# AUDIO_CODEC.net
KiCad netlist of a schematic drawn in Altium Designer
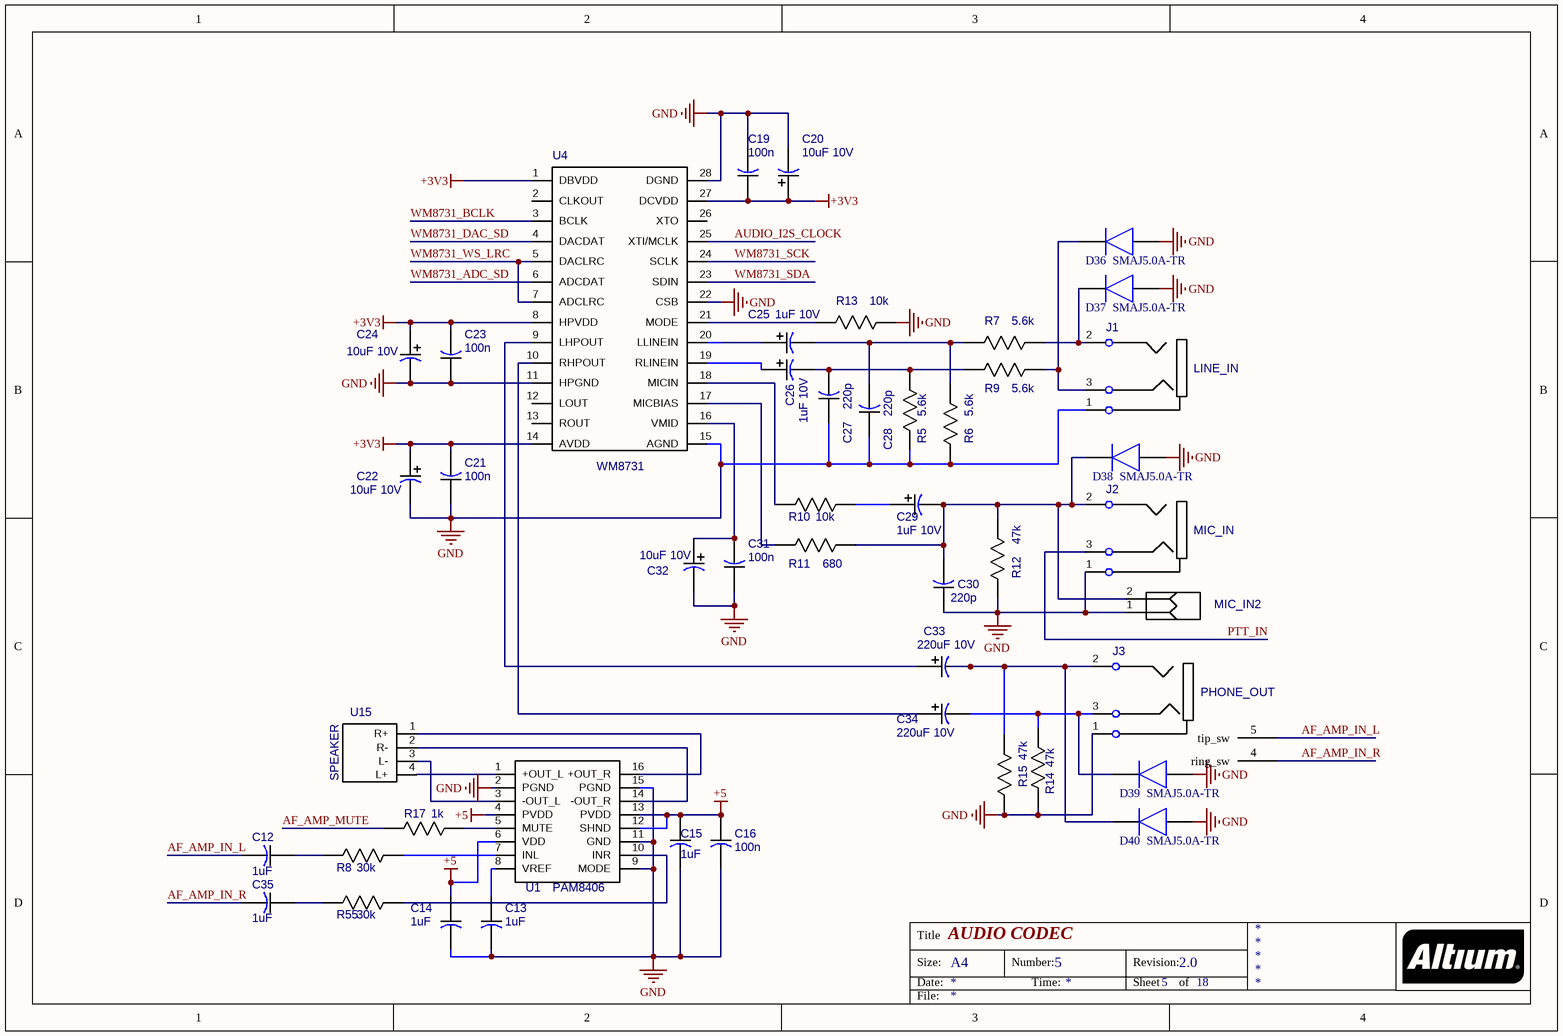
[diagram p0: AUDIO CODEC.SchDoc]

(export (version "E")
  (design (tool "Eeschema 10.0.6"))
  (components
    (comp (ref "C12")
      (value "1uF")
      (footprint "CAP_0805")
      (description "CAP_0805")
      (libsource (lib "*") (part "CAP_0805"))
    )
    (comp (ref "C13")
      (value "1uF")
      (footprint "CAP_0805")
      (description "CAP_0805")
      (libsource (lib "*") (part "CAP_0805"))
    )
    (comp (ref "C14")
      (value "1uF")
      (footprint "CAP_0805")
      (description "CAP_0805")
      (libsource (lib "*") (part "CAP_0805"))
    )
    (comp (ref "C15")
      (value "1uF")
      (footprint "CAP_0805")
      (description "CAP_0805")
      (libsource (lib "*") (part "CAP_0805"))
    )
    (comp (ref "C16")
      (value "100n")
      (footprint "CAP_0805")
      (description "CAP_0805")
      (libsource (lib "*") (part "CAP_0805"))
    )
    (comp (ref "C19")
      (value "100n")
      (footprint "CAP_0805")
      (description "CAP_0805")
      (libsource (lib "*") (part "CAP_0805"))
    )
    (comp (ref "C20")
      (value "10uF 10V")
      (footprint "CAPAE_4.3x4.3h5.4")
      (description "CAPAE_4.3x4.3h5.4")
      (libsource (lib "*") (part "CAPAE_4.3x4.3h5.4"))
    )
    (comp (ref "C21")
      (value "100n")
      (footprint "CAP_0805")
      (description "CAP_0805")
      (libsource (lib "*") (part "CAP_0805"))
    )
    (comp (ref "C22")
      (value "10uF 10V")
      (footprint "CAPAE_4.3x4.3h5.4")
      (description "CAPAE_4.3x4.3h5.4")
      (libsource (lib "*") (part "CAPAE_4.3x4.3h5.4"))
    )
    (comp (ref "C23")
      (value "100n")
      (footprint "CAP_0805")
      (description "CAP_0805")
      (libsource (lib "*") (part "CAP_0805"))
    )
    (comp (ref "C24")
      (value "10uF 10V")
      (footprint "CAPAE_4.3x4.3h5.4")
      (description "CAPAE_4.3x4.3h5.4")
      (libsource (lib "*") (part "CAPAE_4.3x4.3h5.4"))
    )
    (comp (ref "C25")
      (value "1uF 10V")
      (footprint "CAPAE_4.3x4.3h5.4")
      (description "CAPAE_4.3x4.3h5.4")
      (libsource (lib "*") (part "CAPAE_4.3x4.3h5.4"))
    )
    (comp (ref "C26")
      (value "1uF 10V")
      (footprint "CAPAE_4.3x4.3h5.4")
      (description "CAPAE_4.3x4.3h5.4")
      (libsource (lib "*") (part "CAPAE_4.3x4.3h5.4"))
    )
    (comp (ref "C27")
      (value "220p")
      (footprint "CAP_0805")
      (description "CAP_0805")
      (libsource (lib "*") (part "CAP_0805"))
    )
    (comp (ref "C28")
      (value "220p")
      (footprint "CAP_0805")
      (description "CAP_0805")
      (libsource (lib "*") (part "CAP_0805"))
    )
    (comp (ref "C29")
      (value "1uF 10V")
      (footprint "CAPAE_4.3x4.3h5.4")
      (description "CAPAE_4.3x4.3h5.4")
      (libsource (lib "*") (part "CAPAE_4.3x4.3h5.4"))
    )
    (comp (ref "C30")
      (value "220p")
      (footprint "CAP_0805")
      (description "CAP_0805")
      (libsource (lib "*") (part "CAP_0805"))
    )
    (comp (ref "C31")
      (value "100n")
      (footprint "CAP_0805")
      (description "CAP_0805")
      (libsource (lib "*") (part "CAP_0805"))
    )
    (comp (ref "C32")
      (value "10uF 10V")
      (footprint "CAPAE_4.3x4.3h5.4")
      (description "CAPAE_4.3x4.3h5.4")
      (libsource (lib "*") (part "CAPAE_4.3x4.3h5.4"))
    )
    (comp (ref "C33")
      (value "220uF 10V")
      (footprint "EEEFC_sizeС")
      (description "CAPAE_4.3x4.3h5.4")
      (libsource (lib "*") (part "CAPAE_4.3x4.3h5.4"))
    )
    (comp (ref "C34")
      (value "220uF 10V")
      (footprint "EEEFC_sizeС")
      (description "CAPAE_4.3x4.3h5.4")
      (libsource (lib "*") (part "CAPAE_4.3x4.3h5.4"))
    )
    (comp (ref "C35")
      (value "1uF")
      (footprint "CAP_0805")
      (description "CAP_0805")
      (libsource (lib "*") (part "CAP_0805"))
    )
    (comp (ref "D36")
      (value "SMAJ5.0A-TR")
      (footprint "SamacSys:SMBJ36CATR")
      (description "Diode")
      (fields
        (field (name "MANUFACTURER_PART_NUMBER") "SMLVT3V3")
        (field (name "MOUSER PART NUMBER") "511-SMLVT3V3")
      )
      (libsource (lib "*") (part "SMLVT3V3"))
    )
    (comp (ref "D37")
      (value "SMAJ5.0A-TR")
      (footprint "SamacSys:SMBJ36CATR")
      (description "Diode")
      (fields
        (field (name "MANUFACTURER_PART_NUMBER") "SMLVT3V3")
        (field (name "MOUSER PART NUMBER") "511-SMLVT3V3")
      )
      (libsource (lib "*") (part "SMLVT3V3"))
    )
    (comp (ref "D38")
      (value "SMAJ5.0A-TR")
      (footprint "SamacSys:SMBJ36CATR")
      (description "Diode")
      (fields
        (field (name "MANUFACTURER_PART_NUMBER") "SMLVT3V3")
        (field (name "MOUSER PART NUMBER") "511-SMLVT3V3")
      )
      (libsource (lib "*") (part "SMLVT3V3"))
    )
    (comp (ref "D39")
      (value "SMAJ5.0A-TR")
      (footprint "SamacSys:SMBJ36CATR")
      (description "Diode")
      (fields
        (field (name "MANUFACTURER_PART_NUMBER") "SMLVT3V3")
        (field (name "MOUSER PART NUMBER") "511-SMLVT3V3")
      )
      (libsource (lib "*") (part "SMLVT3V3"))
    )
    (comp (ref "D40")
      (value "SMAJ5.0A-TR")
      (footprint "SamacSys:SMBJ36CATR")
      (description "Diode")
      (fields
        (field (name "MANUFACTURER_PART_NUMBER") "SMLVT3V3")
        (field (name "MOUSER PART NUMBER") "511-SMLVT3V3")
      )
      (libsource (lib "*") (part "SMLVT3V3"))
    )
    (comp (ref "J1")
      (value "LINE_IN")
      (footprint "SJ1-3525NG")
      (description "SJ1-3525NG")
      (libsource (lib "*") (part "SJ1-3523N"))
    )
    (comp (ref "J2")
      (value "MIC_IN")
      (footprint "SJ1-3525NG")
      (description "SJ1-3525NG")
      (libsource (lib "*") (part "SJ1-3523N"))
    )
    (comp (ref "J3")
      (value "PHONE_OUT")
      (footprint "SJ1-3525NG")
      (description "SJ1-3525NG")
      (libsource (lib "") (part "SJ1-3523N_1"))
    )
    (comp (ref "MIС_IN2")
      (value "MIС_IN2")
      (footprint "51022-0200")
      (description "2 Pin")
      (libsource (lib "*") (part "51022-0200"))
    )
    (comp (ref "R5")
      (value "5.6k")
      (footprint "RES_0805")
      (description "RES_0805")
      (libsource (lib "*") (part "RES_0805"))
    )
    (comp (ref "R6")
      (value "5.6k")
      (footprint "RES_0805")
      (description "RES_0805")
      (libsource (lib "*") (part "RES_0805"))
    )
    (comp (ref "R7")
      (value "5.6k")
      (footprint "RES_0805")
      (description "RES_0805")
      (libsource (lib "*") (part "RES_0805"))
    )
    (comp (ref "R8")
      (value "30k")
      (footprint "RES_0805")
      (description "RES_0805")
      (libsource (lib "*") (part "RES_0805"))
    )
    (comp (ref "R9")
      (value "5.6k")
      (footprint "RES_0805")
      (description "RES_0805")
      (libsource (lib "*") (part "RES_0805"))
    )
    (comp (ref "R10")
      (value "10k")
      (footprint "RES_0805")
      (description "RES_0805")
      (libsource (lib "*") (part "RES_0805"))
    )
    (comp (ref "R11")
      (value "680")
      (footprint "RES_0805")
      (description "RES_0805")
      (libsource (lib "*") (part "RES_0805"))
    )
    (comp (ref "R12")
      (value "47k")
      (footprint "RES_0805")
      (description "RES_0805")
      (libsource (lib "*") (part "RES_0805"))
    )
    (comp (ref "R13")
      (value "10k")
      (footprint "RES_0805")
      (description "RES_0805")
      (libsource (lib "*") (part "RES_0805"))
    )
    (comp (ref "R14")
      (value "47k")
      (footprint "RES_0805")
      (description "RES_0805")
      (libsource (lib "*") (part "RES_0805"))
    )
    (comp (ref "R15")
      (value "47k")
      (footprint "RES_0805")
      (description "RES_0805")
      (libsource (lib "*") (part "RES_0805"))
    )
    (comp (ref "R17")
      (value "1k")
      (footprint "RES_0805")
      (description "RES_0805")
      (libsource (lib "*") (part "RES_0805"))
    )
    (comp (ref "R55")
      (value "30k")
      (footprint "RES_0805")
      (description "RES_0805")
      (libsource (lib "*") (part "RES_0805"))
    )
    (comp (ref "U1") (value "PAM8406") (footprint "PAM8403") (libsource (lib "MOTHERBOARD") (part "PAM8406")))
    (comp (ref "U4") (value "WM8731") (footprint "WM8731") (libsource (lib "*") (part "WM8731")))
    (comp (ref "U15")
      (value "SPEAKER")
      (footprint "speaker conn")
      (description "4 pins conn")
      (libsource (lib "MOTHERBOARD") (part "speaker conn"))
    )
  )
  (nets
    (net (code "1") (name "+3V3") (class "Default")
      (node (ref "C19") (pin "1") (pinfunction "1_1") (pintype "passive"))
      (node (ref "C20") (pin "1") (pinfunction "PLUS_1") (pintype "passive"))
      (node (ref "C21") (pin "2") (pinfunction "2_2") (pintype "passive"))
      (node (ref "C22") (pin "1") (pinfunction "PLUS_1") (pintype "passive"))
      (node (ref "C23") (pin "2") (pinfunction "2_2") (pintype "passive"))
      (node (ref "C24") (pin "1") (pinfunction "PLUS_1") (pintype "passive"))
      (node (ref "U4") (pin "1") (pinfunction "DBVDD_1") (pintype "passive"))
      (node (ref "U4") (pin "14") (pinfunction "AVDD_14") (pintype "passive"))
      (node (ref "U4") (pin "27") (pinfunction "DCVDD_27") (pintype "passive"))
      (node (ref "U4") (pin "8") (pinfunction "HPVDD_8") (pintype "passive"))
    )
    (net (code "2") (name "+5") (class "Default")
      (node (ref "C14") (pin "1") (pinfunction "1_1") (pintype "passive"))
      (node (ref "C15") (pin "1") (pinfunction "1_1") (pintype "passive"))
      (node (ref "C16") (pin "1") (pinfunction "1_1") (pintype "passive"))
      (node (ref "U1") (pin "12") (pinfunction "SHND_12") (pintype "passive"))
      (node (ref "U1") (pin "13") (pinfunction "PVDD_13") (pintype "passive"))
      (node (ref "U1") (pin "4") (pinfunction "PVDD_4") (pintype "passive"))
      (node (ref "U1") (pin "6") (pinfunction "VDD_6") (pintype "passive"))
    )
    (net (code "3") (name "/AF_AMP_IN_L") (class "Default")
      (node (ref "C12") (pin "2") (pinfunction "2_2") (pintype "passive"))
      (node (ref "J3") (pin "5") (pinfunction "tip_sw_5") (pintype "passive"))
    )
    (net (code "4") (name "/AF_AMP_IN_R") (class "Default")
      (node (ref "C35") (pin "2") (pinfunction "2_2") (pintype "passive"))
      (node (ref "J3") (pin "4") (pinfunction "ring_sw_4") (pintype "passive"))
    )
    (net (code "5") (name "/AF_AMP_MUTE") (class "Default")
      (node (ref "R17") (pin "2") (pinfunction "2_2") (pintype "passive"))
    )
    (net (code "6") (name "/AUDIO_I2S_CLOCK") (class "Default")
      (node (ref "U4") (pin "25") (pinfunction "XTI/MCLK_25") (pintype "passive"))
    )
    (net (code "7") (name "/PTT_IN") (class "Default")
      (node (ref "J2") (pin "3") (pinfunction "ring_3") (pintype "passive"))
    )
    (net (code "8") (name "/WM8731_ADC_SD") (class "Default")
      (node (ref "U4") (pin "6") (pinfunction "ADCDAT_6") (pintype "passive"))
    )
    (net (code "9") (name "/WM8731_BCLK") (class "Default")
      (node (ref "U4") (pin "3") (pinfunction "BCLK_3") (pintype "passive"))
    )
    (net (code "10") (name "/WM8731_DAC_SD") (class "Default")
      (node (ref "U4") (pin "4") (pinfunction "DACDAT_4") (pintype "passive"))
    )
    (net (code "11") (name "/WM8731_SCK") (class "Default")
      (node (ref "U4") (pin "24") (pinfunction "SCLK_24") (pintype "passive"))
    )
    (net (code "12") (name "/WM8731_SDA") (class "Default")
      (node (ref "U4") (pin "23") (pinfunction "SDIN_23") (pintype "passive"))
    )
    (net (code "13") (name "/WM8731_WS_LRC") (class "Default")
      (node (ref "U4") (pin "5") (pinfunction "DACLRC_5") (pintype "passive"))
      (node (ref "U4") (pin "7") (pinfunction "ADCLRC_7") (pintype "passive"))
    )
    (net (code "14") (name "GND") (class "Default")
      (node (ref "C13") (pin "2") (pinfunction "2_2") (pintype "passive"))
      (node (ref "C14") (pin "2") (pinfunction "2_2") (pintype "passive"))
      (node (ref "C15") (pin "2") (pinfunction "2_2") (pintype "passive"))
      (node (ref "C16") (pin "2") (pinfunction "2_2") (pintype "passive"))
      (node (ref "C19") (pin "2") (pinfunction "2_2") (pintype "passive"))
      (node (ref "C20") (pin "2") (pinfunction "MINUS_2") (pintype "passive"))
      (node (ref "C21") (pin "1") (pinfunction "1_1") (pintype "passive"))
      (node (ref "C22") (pin "2") (pinfunction "MINUS_2") (pintype "passive"))
      (node (ref "C23") (pin "1") (pinfunction "1_1") (pintype "passive"))
      (node (ref "C24") (pin "2") (pinfunction "MINUS_2") (pintype "passive"))
      (node (ref "C27") (pin "1") (pinfunction "1_1") (pintype "passive"))
      (node (ref "C28") (pin "1") (pinfunction "1_1") (pintype "passive"))
      (node (ref "C30") (pin "1") (pinfunction "1_1") (pintype "passive"))
      (node (ref "C31") (pin "1") (pinfunction "1_1") (pintype "passive"))
      (node (ref "C32") (pin "2") (pinfunction "MINUS_2") (pintype "passive"))
      (node (ref "D36") (pin "2") (pinfunction "A_2") (pintype "passive"))
      (node (ref "D37") (pin "2") (pinfunction "A_2") (pintype "passive"))
      (node (ref "D38") (pin "2") (pinfunction "A_2") (pintype "passive"))
      (node (ref "D39") (pin "2") (pinfunction "A_2") (pintype "passive"))
      (node (ref "D40") (pin "2") (pinfunction "A_2") (pintype "passive"))
      (node (ref "J1") (pin "1") (pinfunction "sleeve_1") (pintype "passive"))
      (node (ref "J2") (pin "1") (pinfunction "sleeve_1") (pintype "passive"))
      (node (ref "J3") (pin "1") (pinfunction "sleeve_1") (pintype "passive"))
      (node (ref "MIС_IN2") (pin "1") (pinfunction "1_1") (pintype "passive"))
      (node (ref "R12") (pin "1") (pinfunction "1_1") (pintype "passive"))
      (node (ref "R13") (pin "1") (pinfunction "1_1") (pintype "passive"))
      (node (ref "R14") (pin "1") (pinfunction "1_1") (pintype "passive"))
      (node (ref "R15") (pin "1") (pinfunction "1_1") (pintype "passive"))
      (node (ref "R5") (pin "1") (pinfunction "1_1") (pintype "passive"))
      (node (ref "R6") (pin "1") (pinfunction "1_1") (pintype "passive"))
      (node (ref "U1") (pin "11") (pinfunction "GND_11") (pintype "passive"))
      (node (ref "U1") (pin "15") (pinfunction "PGND_15") (pintype "passive"))
      (node (ref "U1") (pin "2") (pinfunction "PGND_2") (pintype "passive"))
      (node (ref "U1") (pin "9") (pinfunction "MODE_9") (pintype "passive"))
      (node (ref "U4") (pin "11") (pinfunction "HPGND_11") (pintype "passive"))
      (node (ref "U4") (pin "15") (pinfunction "AGND_15") (pintype "passive"))
      (node (ref "U4") (pin "22") (pinfunction "CSB_22") (pintype "passive"))
      (node (ref "U4") (pin "28") (pinfunction "DGND_28") (pintype "passive"))
    )
    (net (code "15") (name "Net-(C12-Pad1)") (class "Default")
      (node (ref "C12") (pin "1") (pinfunction "1_1") (pintype "passive"))
      (node (ref "R8") (pin "2") (pinfunction "2_2") (pintype "passive"))
    )
    (net (code "16") (name "Net-(C25-MINUS)") (class "Default")
      (node (ref "C25") (pin "2") (pinfunction "MINUS_2") (pintype "passive"))
      (node (ref "C28") (pin "2") (pinfunction "2_2") (pintype "passive"))
      (node (ref "R6") (pin "2") (pinfunction "2_2") (pintype "passive"))
      (node (ref "R7") (pin "2") (pinfunction "2_2") (pintype "passive"))
    )
    (net (code "17") (name "Net-(C25-PLUS)") (class "Default")
      (node (ref "C25") (pin "1") (pinfunction "PLUS_1") (pintype "passive"))
      (node (ref "U4") (pin "20") (pinfunction "LLINEIN_20") (pintype "passive"))
    )
    (net (code "18") (name "Net-(C26-MINUS)") (class "Default")
      (node (ref "C26") (pin "2") (pinfunction "MINUS_2") (pintype "passive"))
      (node (ref "C27") (pin "2") (pinfunction "2_2") (pintype "passive"))
      (node (ref "R5") (pin "2") (pinfunction "2_2") (pintype "passive"))
      (node (ref "R9") (pin "2") (pinfunction "2_2") (pintype "passive"))
    )
    (net (code "19") (name "Net-(C26-PLUS)") (class "Default")
      (node (ref "C26") (pin "1") (pinfunction "PLUS_1") (pintype "passive"))
      (node (ref "U4") (pin "19") (pinfunction "RLINEIN_19") (pintype "passive"))
    )
    (net (code "20") (name "Net-(C29-MINUS)") (class "Default")
      (node (ref "C29") (pin "2") (pinfunction "MINUS_2") (pintype "passive"))
      (node (ref "C30") (pin "2") (pinfunction "2_2") (pintype "passive"))
      (node (ref "D38") (pin "1") (pinfunction "K_1") (pintype "passive"))
      (node (ref "J2") (pin "2") (pinfunction "tip_2") (pintype "passive"))
      (node (ref "MIС_IN2") (pin "2") (pinfunction "2_2") (pintype "passive"))
      (node (ref "R11") (pin "1") (pinfunction "1_1") (pintype "passive"))
      (node (ref "R12") (pin "2") (pinfunction "2_2") (pintype "passive"))
    )
    (net (code "21") (name "Net-(C29-PLUS)") (class "Default")
      (node (ref "C29") (pin "1") (pinfunction "PLUS_1") (pintype "passive"))
      (node (ref "R10") (pin "1") (pinfunction "1_1") (pintype "passive"))
    )
    (net (code "22") (name "Net-(C32-PLUS)") (class "Default")
      (node (ref "C31") (pin "2") (pinfunction "2_2") (pintype "passive"))
      (node (ref "C32") (pin "1") (pinfunction "PLUS_1") (pintype "passive"))
      (node (ref "U4") (pin "16") (pinfunction "VMID_16") (pintype "passive"))
    )
    (net (code "23") (name "Net-(C33-MINUS)") (class "Default")
      (node (ref "C33") (pin "2") (pinfunction "MINUS_2") (pintype "passive"))
      (node (ref "D40") (pin "1") (pinfunction "K_1") (pintype "passive"))
      (node (ref "J3") (pin "2") (pinfunction "tip_2") (pintype "passive"))
      (node (ref "R15") (pin "2") (pinfunction "2_2") (pintype "passive"))
    )
    (net (code "24") (name "Net-(C33-PLUS)") (class "Default")
      (node (ref "C33") (pin "1") (pinfunction "PLUS_1") (pintype "passive"))
      (node (ref "U4") (pin "9") (pinfunction "LHPOUT_9") (pintype "passive"))
    )
    (net (code "25") (name "Net-(C34-MINUS)") (class "Default")
      (node (ref "C34") (pin "2") (pinfunction "MINUS_2") (pintype "passive"))
      (node (ref "D39") (pin "1") (pinfunction "K_1") (pintype "passive"))
      (node (ref "J3") (pin "3") (pinfunction "ring_3") (pintype "passive"))
      (node (ref "R14") (pin "2") (pinfunction "2_2") (pintype "passive"))
    )
    (net (code "26") (name "Net-(C34-PLUS)") (class "Default")
      (node (ref "C34") (pin "1") (pinfunction "PLUS_1") (pintype "passive"))
      (node (ref "U4") (pin "10") (pinfunction "RHPOUT_10") (pintype "passive"))
    )
    (net (code "27") (name "Net-(C35-Pad1)") (class "Default")
      (node (ref "C35") (pin "1") (pinfunction "1_1") (pintype "passive"))
      (node (ref "R55") (pin "2") (pinfunction "2_2") (pintype "passive"))
    )
    (net (code "28") (name "Net-(D36-K)") (class "Default")
      (node (ref "D36") (pin "1") (pinfunction "K_1") (pintype "passive"))
      (node (ref "J1") (pin "3") (pinfunction "ring_3") (pintype "passive"))
      (node (ref "R9") (pin "1") (pinfunction "1_1") (pintype "passive"))
    )
    (net (code "29") (name "Net-(D37-K)") (class "Default")
      (node (ref "D37") (pin "1") (pinfunction "K_1") (pintype "passive"))
      (node (ref "J1") (pin "2") (pinfunction "tip_2") (pintype "passive"))
      (node (ref "R7") (pin "1") (pinfunction "1_1") (pintype "passive"))
    )
    (net (code "30") (name "Net-(U1-+OUT_L)") (class "Default")
      (node (ref "U1") (pin "1") (pinfunction "+OUT_L_1") (pintype "passive"))
      (node (ref "U15") (pin "4") (pinfunction "L+_4") (pintype "passive"))
    )
    (net (code "31") (name "Net-(U1-+OUT_R)") (class "Default")
      (node (ref "U1") (pin "16") (pinfunction "+OUT_R_16") (pintype "passive"))
      (node (ref "U15") (pin "1") (pinfunction "R+_1") (pintype "passive"))
    )
    (net (code "32") (name "Net-(U1--OUT_L)") (class "Default")
      (node (ref "U1") (pin "3") (pinfunction "-OUT_L_3") (pintype "passive"))
      (node (ref "U15") (pin "3") (pinfunction "L-_3") (pintype "passive"))
    )
    (net (code "33") (name "Net-(U1--OUT_R)") (class "Default")
      (node (ref "U1") (pin "14") (pinfunction "-OUT_R_14") (pintype "passive"))
      (node (ref "U15") (pin "2") (pinfunction "R-_2") (pintype "passive"))
    )
    (net (code "34") (name "Net-(U1-INL)") (class "Default")
      (node (ref "R8") (pin "1") (pinfunction "1_1") (pintype "passive"))
      (node (ref "U1") (pin "7") (pinfunction "INL_7") (pintype "passive"))
    )
    (net (code "35") (name "Net-(U1-INR)") (class "Default")
      (node (ref "R55") (pin "1") (pinfunction "1_1") (pintype "passive"))
      (node (ref "U1") (pin "10") (pinfunction "INR_10") (pintype "passive"))
    )
    (net (code "36") (name "Net-(U1-MUTE)") (class "Default")
      (node (ref "R17") (pin "1") (pinfunction "1_1") (pintype "passive"))
      (node (ref "U1") (pin "5") (pinfunction "MUTE_5") (pintype "passive"))
    )
    (net (code "37") (name "Net-(U1-VREF)") (class "Default")
      (node (ref "C13") (pin "1") (pinfunction "1_1") (pintype "passive"))
      (node (ref "U1") (pin "8") (pinfunction "VREF_8") (pintype "passive"))
    )
    (net (code "38") (name "Net-(U4-MICBIAS)") (class "Default")
      (node (ref "R11") (pin "2") (pinfunction "2_2") (pintype "passive"))
      (node (ref "U4") (pin "17") (pinfunction "MICBIAS_17") (pintype "passive"))
    )
    (net (code "39") (name "Net-(U4-MICIN)") (class "Default")
      (node (ref "R10") (pin "2") (pinfunction "2_2") (pintype "passive"))
      (node (ref "U4") (pin "18") (pinfunction "MICIN_18") (pintype "passive"))
    )
    (net (code "40") (name "Net-(U4-MODE)") (class "Default")
      (node (ref "R13") (pin "2") (pinfunction "2_2") (pintype "passive"))
      (node (ref "U4") (pin "21") (pinfunction "MODE_21") (pintype "passive"))
    )
    (net (code "41") (name "unconnected-(U4-CLKOUT-Pad2)") (class "Default")
      (node (ref "U4") (pin "2") (pinfunction "CLKOUT_2") (pintype "passive"))
    )
    (net (code "42") (name "unconnected-(U4-LOUT-Pad12)") (class "Default")
      (node (ref "U4") (pin "12") (pinfunction "LOUT_12") (pintype "passive"))
    )
    (net (code "43") (name "unconnected-(U4-ROUT-Pad13)") (class "Default")
      (node (ref "U4") (pin "13") (pinfunction "ROUT_13") (pintype "passive"))
    )
    (net (code "44") (name "unconnected-(U4-XTO-Pad26)") (class "Default")
      (node (ref "U4") (pin "26") (pinfunction "XTO_26") (pintype "passive"))
    )
  )
)
